# relay_pwm.net
KiCad netlist of a schematic drawn in EAGLE
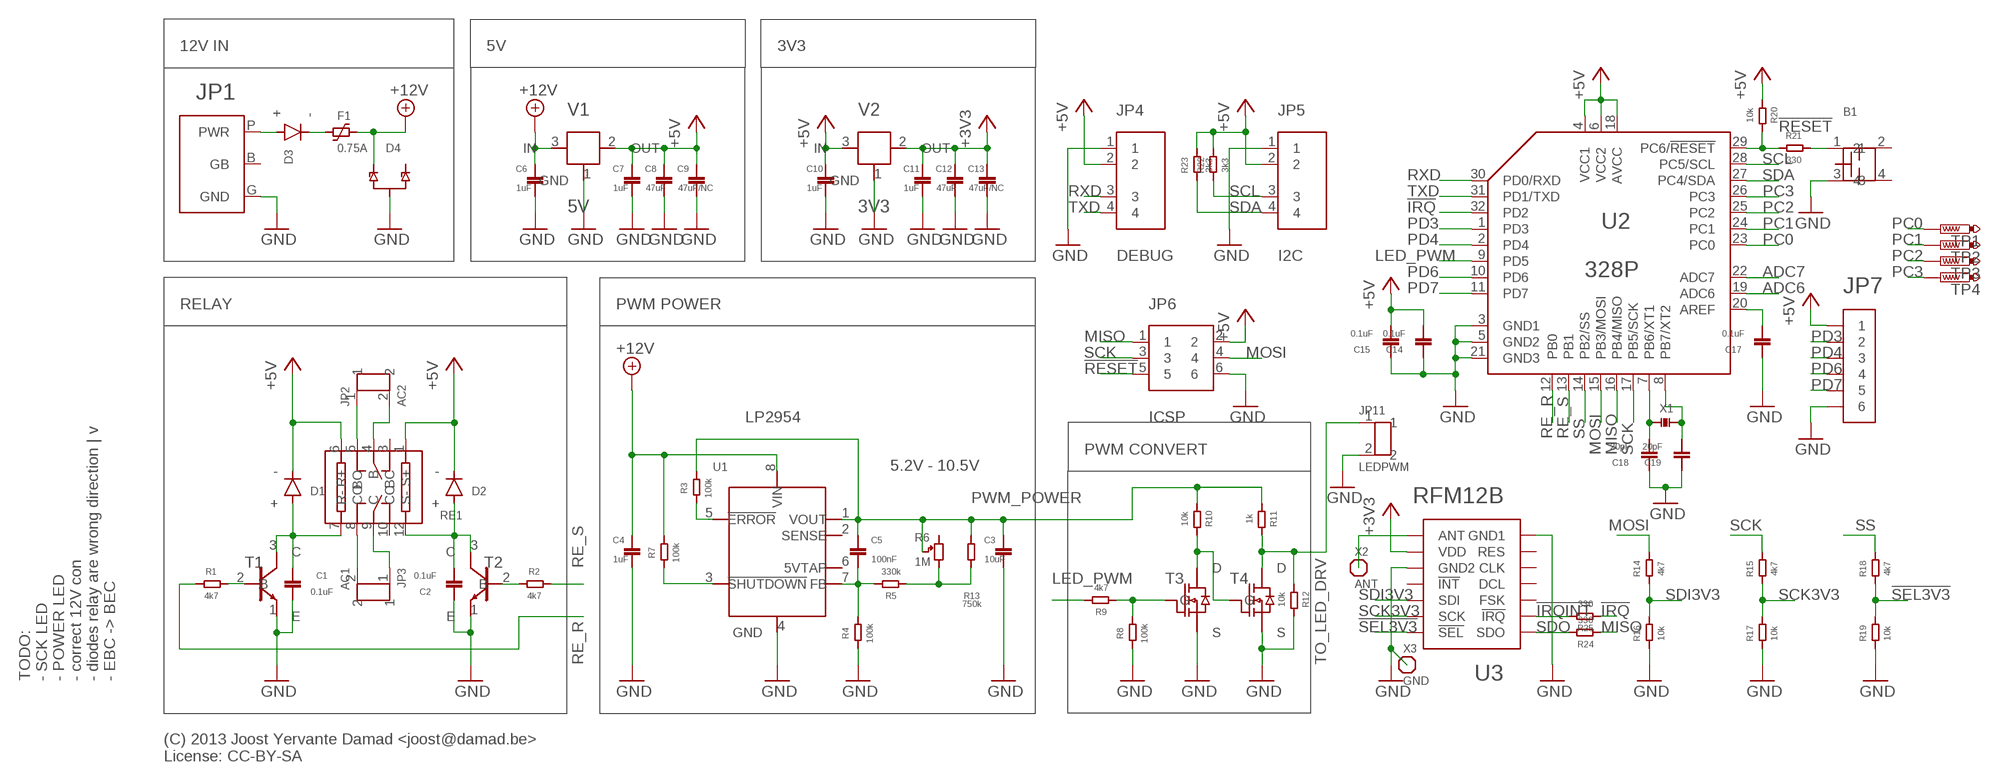
[diagram p0: schematic, sheet 1]

(export (version "E")
  (design (tool "Eeschema 10.0.6"))
  (components
    (comp (ref "B1")
      (value "BUTTON_ALPS_5.2MM_SMD")
      (footprint "eagle-import:BUTTON_ALPS_SMD_5.2MM_SKQG")
      (libsource (lib "eagle-import") (part "BUTTON_ALPS_5.2MM_SMD"))
    )
    (comp (ref "C1")
      (value "0.1uF")
      (footprint "eagle-import:0603@1")
      (libsource (lib "eagle-import") (part "C0603"))
    )
    (comp (ref "C2")
      (value "0.1uF")
      (footprint "eagle-import:0603@1")
      (libsource (lib "eagle-import") (part "C0603"))
    )
    (comp (ref "C3")
      (value "10uF")
      (footprint "eagle-import:1206")
      (libsource (lib "eagle-import") (part "CAPACITOR1206"))
    )
    (comp (ref "C4")
      (value "1uF")
      (footprint "eagle-import:0603")
      (libsource (lib "eagle-import") (part "CAPACITOR0603"))
    )
    (comp (ref "C5")
      (value "100nF")
      (footprint "eagle-import:0603")
      (libsource (lib "eagle-import") (part "CAPACITOR0603"))
    )
    (comp (ref "C6")
      (value "1uF")
      (footprint "eagle-import:0603")
      (libsource (lib "eagle-import") (part "CAPACITOR0603"))
    )
    (comp (ref "C7")
      (value "1uF")
      (footprint "eagle-import:0603")
      (libsource (lib "eagle-import") (part "CAPACITOR0603"))
    )
    (comp (ref "C8")
      (value "47uF")
      (footprint "eagle-import:1206")
      (libsource (lib "eagle-import") (part "CAPACITOR1206"))
    )
    (comp (ref "C9")
      (value "47uF/NC")
      (footprint "eagle-import:1206")
      (libsource (lib "eagle-import") (part "CAPACITOR1206"))
    )
    (comp (ref "C10")
      (value "1uF")
      (footprint "eagle-import:0603")
      (libsource (lib "eagle-import") (part "CAPACITOR0603"))
    )
    (comp (ref "C11")
      (value "1uF")
      (footprint "eagle-import:0603")
      (libsource (lib "eagle-import") (part "CAPACITOR0603"))
    )
    (comp (ref "C12")
      (value "47uF")
      (footprint "eagle-import:1206")
      (libsource (lib "eagle-import") (part "CAPACITOR1206"))
    )
    (comp (ref "C13")
      (value "47uF/NC")
      (footprint "eagle-import:1206")
      (libsource (lib "eagle-import") (part "CAPACITOR1206"))
    )
    (comp (ref "C14")
      (value "0.1uF")
      (footprint "eagle-import:0603@1")
      (libsource (lib "eagle-import") (part "C0603"))
    )
    (comp (ref "C15")
      (value "0.1uF")
      (footprint "eagle-import:0603@1")
      (libsource (lib "eagle-import") (part "C0603"))
    )
    (comp (ref "C17")
      (value "0.1uF")
      (footprint "eagle-import:0603@1")
      (libsource (lib "eagle-import") (part "C0603"))
    )
    (comp (ref "C18")
      (value "20pF")
      (footprint "eagle-import:0603@1")
      (libsource (lib "eagle-import") (part "C0603"))
    )
    (comp (ref "C19")
      (value "20pF")
      (footprint "eagle-import:0603@1")
      (libsource (lib "eagle-import") (part "C0603"))
    )
    (comp (ref "D1")
      (value "DIODE")
      (footprint "eagle-import:TAIW_SEM_DIODE")
      (libsource (lib "eagle-import") (part "DIODE"))
    )
    (comp (ref "D2")
      (value "DIODE")
      (footprint "eagle-import:TAIW_SEM_DIODE")
      (libsource (lib "eagle-import") (part "DIODE"))
    )
    (comp (ref "D3")
      (value "DIODE")
      (footprint "eagle-import:TAIW_SEM_DIODE")
      (libsource (lib "eagle-import") (part "DIODE"))
    )
    (comp (ref "D4")
      (value "DUAL_TVSSOT-23")
      (footprint "eagle-import:SOT-23")
      (libsource (lib "eagle-import") (part "DUAL_TVSSOT-23"))
    )
    (comp (ref "F1")
      (value "0.75A")
      (footprint "eagle-import:TE_POLYFUSE_1812")
      (libsource (lib "eagle-import") (part "TE_POLYFUSE_1812"))
    )
    (comp (ref "JP1")
      (value "POWER_PLUG_2.1MM")
      (footprint "eagle-import:POWER_PLUG_2.1MM")
      (libsource (lib "eagle-import") (part "POWER_PLUG_2.1MM"))
    )
    (comp (ref "JP2")
      (value "AC2")
      (footprint "eagle-import:WAGO_500_SCREW_TERMINAL_2_PIN")
      (libsource (lib "eagle-import") (part "WAGO500-2PIN"))
    )
    (comp (ref "JP3")
      (value "AC1")
      (footprint "eagle-import:WAGO_500_SCREW_TERMINAL_2_PIN")
      (libsource (lib "eagle-import") (part "WAGO500-2PIN"))
    )
    (comp (ref "JP4")
      (value "DEBUG")
      (footprint "eagle-import:PIN_1X4")
      (libsource (lib "eagle-import") (part "PIN1X4PTH2.54"))
    )
    (comp (ref "JP5")
      (value "I2C")
      (footprint "eagle-import:JST-S-4B-XH-A")
      (libsource (lib "eagle-import") (part "PIN1X4JSTSIDE"))
    )
    (comp (ref "JP6")
      (value "ICSP")
      (footprint "eagle-import:PIN_2X3_ALT")
      (libsource (lib "eagle-import") (part "PIN2X32X3ALT"))
    )
    (comp (ref "JP7")
      (value "PIN1X6")
      (footprint "eagle-import:PIN_1X6")
      (libsource (lib "eagle-import") (part "PIN1X6"))
    )
    (comp (ref "JP11")
      (value "LEDPWM")
      (footprint "eagle-import:WAGO_500_SCREW_TERMINAL_2_PIN")
      (libsource (lib "eagle-import") (part "WAGO500-2PIN"))
    )
    (comp (ref "R1")
      (value "4k7")
      (footprint "eagle-import:0603")
      (libsource (lib "eagle-import") (part "RESISTOR0603"))
    )
    (comp (ref "R2")
      (value "4k7")
      (footprint "eagle-import:0603")
      (libsource (lib "eagle-import") (part "RESISTOR0603"))
    )
    (comp (ref "R3")
      (value "100k")
      (footprint "eagle-import:0603")
      (libsource (lib "eagle-import") (part "RESISTOR0603"))
    )
    (comp (ref "R4")
      (value "100k")
      (footprint "eagle-import:0603")
      (libsource (lib "eagle-import") (part "RESISTOR0603"))
    )
    (comp (ref "R5")
      (value "330k")
      (footprint "eagle-import:0603")
      (libsource (lib "eagle-import") (part "RESISTOR0603"))
    )
    (comp (ref "R6")
      (value "1M")
      (footprint "eagle-import:SMT_TRIMMER_PANASONIC_EVM3Y")
      (libsource (lib "eagle-import") (part "TRIMMER"))
    )
    (comp (ref "R7")
      (value "100k")
      (footprint "eagle-import:0603")
      (libsource (lib "eagle-import") (part "RESISTOR0603"))
    )
    (comp (ref "R8")
      (value "100k")
      (footprint "eagle-import:0603")
      (libsource (lib "eagle-import") (part "RESISTOR0603"))
    )
    (comp (ref "R9")
      (value "4k7")
      (footprint "eagle-import:0603")
      (libsource (lib "eagle-import") (part "RESISTOR0603"))
    )
    (comp (ref "R10")
      (value "10k")
      (footprint "eagle-import:0603")
      (libsource (lib "eagle-import") (part "RESISTOR0603"))
    )
    (comp (ref "R11")
      (value "1k")
      (footprint "eagle-import:0603")
      (libsource (lib "eagle-import") (part "RESISTOR0603"))
    )
    (comp (ref "R12")
      (value "10k")
      (footprint "eagle-import:0603")
      (libsource (lib "eagle-import") (part "RESISTOR0603"))
    )
    (comp (ref "R13")
      (value "750k")
      (footprint "eagle-import:0603")
      (libsource (lib "eagle-import") (part "RESISTOR0603"))
    )
    (comp (ref "R14")
      (value "4k7")
      (footprint "eagle-import:0603")
      (libsource (lib "eagle-import") (part "RESISTOR0603"))
    )
    (comp (ref "R15")
      (value "4k7")
      (footprint "eagle-import:0603")
      (libsource (lib "eagle-import") (part "RESISTOR0603"))
    )
    (comp (ref "R16")
      (value "10k")
      (footprint "eagle-import:0603")
      (libsource (lib "eagle-import") (part "RESISTOR0603"))
    )
    (comp (ref "R17")
      (value "10k")
      (footprint "eagle-import:0603")
      (libsource (lib "eagle-import") (part "RESISTOR0603"))
    )
    (comp (ref "R18")
      (value "4k7")
      (footprint "eagle-import:0603")
      (libsource (lib "eagle-import") (part "RESISTOR0603"))
    )
    (comp (ref "R19")
      (value "10k")
      (footprint "eagle-import:0603")
      (libsource (lib "eagle-import") (part "RESISTOR0603"))
    )
    (comp (ref "R20")
      (value "10k")
      (footprint "eagle-import:0603")
      (libsource (lib "eagle-import") (part "RESISTOR0603"))
    )
    (comp (ref "R21")
      (value "330")
      (footprint "eagle-import:0603")
      (libsource (lib "eagle-import") (part "RESISTOR0603"))
    )
    (comp (ref "R22")
      (value "3k3")
      (footprint "eagle-import:0603")
      (libsource (lib "eagle-import") (part "RESISTOR0603"))
    )
    (comp (ref "R23")
      (value "3k3")
      (footprint "eagle-import:0603")
      (libsource (lib "eagle-import") (part "RESISTOR0603"))
    )
    (comp (ref "R24")
      (value "330")
      (footprint "eagle-import:0603")
      (libsource (lib "eagle-import") (part "RESISTOR0603"))
    )
    (comp (ref "R25")
      (value "330")
      (footprint "eagle-import:0603")
      (libsource (lib "eagle-import") (part "RESISTOR0603"))
    )
    (comp (ref "RE1")
      (value "RELAY_TE_V23079_THT_STD_2C")
      (footprint "eagle-import:RELAY_TE_V23079_THT_STANDARD_BISTABLE_2_COIL")
      (libsource (lib "eagle-import") (part "RELAY_TE_V23079_THT_STD_2C"))
    )
    (comp (ref "T1")
      (value "TRANSISTOR-BJT-NPNEBC")
      (footprint "eagle-import:SOT-23")
      (libsource (lib "eagle-import") (part "TRANSISTOR-BJT-NPNEBC"))
    )
    (comp (ref "T2")
      (value "TRANSISTOR-BJT-NPNEBC")
      (footprint "eagle-import:SOT-23")
      (libsource (lib "eagle-import") (part "TRANSISTOR-BJT-NPNEBC"))
    )
    (comp (ref "T3")
      (value "MOSFET-N-ENHGSD")
      (footprint "eagle-import:SOT-23")
      (libsource (lib "eagle-import") (part "MOSFET-N-ENHGSD"))
    )
    (comp (ref "T4")
      (value "MOSFET-N-ENHGSD")
      (footprint "eagle-import:SOT-23")
      (libsource (lib "eagle-import") (part "MOSFET-N-ENHGSD"))
    )
    (comp (ref "TP1")
      (value "PTR1B1,27")
      (footprint "eagle-import:B1,27")
      (libsource (lib "eagle-import") (part "PTR1B1,27"))
    )
    (comp (ref "TP2")
      (value "PTR1B1,27")
      (footprint "eagle-import:B1,27")
      (libsource (lib "eagle-import") (part "PTR1B1,27"))
    )
    (comp (ref "TP3")
      (value "PTR1B1,27")
      (footprint "eagle-import:B1,27")
      (libsource (lib "eagle-import") (part "PTR1B1,27"))
    )
    (comp (ref "TP4")
      (value "PTR1B1,27")
      (footprint "eagle-import:B1,27")
      (libsource (lib "eagle-import") (part "PTR1B1,27"))
    )
    (comp (ref "U1")
      (value "LP2954")
      (footprint "eagle-import:TI_LP2954_SO8")
      (libsource (lib "eagle-import") (part "LP2954"))
    )
    (comp (ref "U2")
      (value "328P")
      (footprint "eagle-import:TQFP32")
      (libsource (lib "eagle-import") (part "ATMEGA328PTQFP32"))
    )
    (comp (ref "U3")
      (value "RFM12B")
      (footprint "eagle-import:RFM12B")
      (libsource (lib "eagle-import") (part "RFM12B"))
    )
    (comp (ref "V1")
      (value "5V")
      (footprint "eagle-import:SOT-23A")
      (libsource (lib "eagle-import") (part "VREG_MCP1703"))
    )
    (comp (ref "V2")
      (value "3V3")
      (footprint "eagle-import:SOT-23A")
      (libsource (lib "eagle-import") (part "VREG_MCP1703"))
    )
    (comp (ref "X1")
      (value "CRYSTAL")
      (footprint "eagle-import:CRYSTAL_2-PAD_5X3.2MM")
      (libsource (lib "eagle-import") (part "CRYSTAL"))
    )
    (comp (ref "X2")
      (value "ANT")
      (footprint "eagle-import:PIN_1X1")
      (libsource (lib "eagle-import") (part "PIN1X1"))
    )
    (comp (ref "X3")
      (value "GND")
      (footprint "eagle-import:PIN_1X1")
      (libsource (lib "eagle-import") (part "PIN1X1"))
    )
  )
  (nets
    (net (code "1") (name "+3V3") (class "Default")
      (node (ref "C11") (pin "2") (pinfunction "1_2") (pintype "passive"))
      (node (ref "C12") (pin "1") (pinfunction "1_1") (pintype "passive"))
      (node (ref "C13") (pin "1") (pinfunction "1_1") (pintype "passive"))
      (node (ref "U3") (pin "VDD") (pinfunction "VDD_VDD") (pintype "bidirectional"))
      (node (ref "V2") (pin "2") (pinfunction "OUT_2") (pintype "bidirectional"))
    )
    (net (code "2") (name "+5V") (class "Default")
      (node (ref "C10") (pin "2") (pinfunction "1_2") (pintype "passive"))
      (node (ref "C14") (pin "1") (pinfunction "2_1") (pintype "passive"))
      (node (ref "C15") (pin "1") (pinfunction "2_1") (pintype "passive"))
      (node (ref "C7") (pin "2") (pinfunction "1_2") (pintype "passive"))
      (node (ref "C8") (pin "1") (pinfunction "1_1") (pintype "passive"))
      (node (ref "C9") (pin "1") (pinfunction "1_1") (pintype "passive"))
      (node (ref "D1") (pin "-") (pinfunction "-_-") (pintype "bidirectional"))
      (node (ref "D2") (pin "-") (pinfunction "-_-") (pintype "bidirectional"))
      (node (ref "JP4") (pin "2") (pinfunction "2_2") (pintype "bidirectional"))
      (node (ref "JP5") (pin "2") (pinfunction "2_2") (pintype "bidirectional"))
      (node (ref "JP6") (pin "2") (pinfunction "2_2") (pintype "bidirectional"))
      (node (ref "JP7") (pin "1") (pinfunction "1_1") (pintype "bidirectional"))
      (node (ref "R20") (pin "1") (pinfunction "1_1") (pintype "passive"))
      (node (ref "R22") (pin "2") (pinfunction "2_2") (pintype "passive"))
      (node (ref "R23") (pin "2") (pinfunction "2_2") (pintype "passive"))
      (node (ref "RE1") (pin "1") (pinfunction "S+_1") (pintype "bidirectional"))
      (node (ref "RE1") (pin "6") (pinfunction "R+_6") (pintype "bidirectional"))
      (node (ref "U2") (pin "18") (pinfunction "AVCC_18") (pintype "bidirectional"))
      (node (ref "U2") (pin "4") (pinfunction "VCC1_4") (pintype "bidirectional"))
      (node (ref "U2") (pin "6") (pinfunction "VCC2_6") (pintype "bidirectional"))
      (node (ref "V1") (pin "2") (pinfunction "OUT_2") (pintype "bidirectional"))
      (node (ref "V2") (pin "3") (pinfunction "IN_3") (pintype "bidirectional"))
    )
    (net (code "3") (name "+12V") (class "Default")
      (node (ref "C4") (pin "2") (pinfunction "1_2") (pintype "passive"))
      (node (ref "C6") (pin "2") (pinfunction "1_2") (pintype "passive"))
      (node (ref "D4") (pin "1") (pinfunction "P1_1") (pintype "bidirectional"))
      (node (ref "F1") (pin "2") (pinfunction "P$2_2") (pintype "bidirectional"))
      (node (ref "R7") (pin "2") (pinfunction "2_2") (pintype "passive"))
      (node (ref "U1") (pin "8") (pinfunction "VIN_8") (pintype "power_in"))
      (node (ref "V1") (pin "3") (pinfunction "IN_3") (pintype "bidirectional"))
    )
    (net (code "4") (name "/ADC6") (class "Default")
      (node (ref "U2") (pin "19") (pinfunction "ADC6_19") (pintype "bidirectional"))
    )
    (net (code "5") (name "/ADC7") (class "Default")
      (node (ref "U2") (pin "22") (pinfunction "ADC7_22") (pintype "bidirectional"))
    )
    (net (code "6") (name "/LED_PWM") (class "Default")
      (node (ref "R9") (pin "2") (pinfunction "2_2") (pintype "passive"))
      (node (ref "U2") (pin "9") (pinfunction "PD5_9") (pintype "bidirectional"))
    )
    (net (code "7") (name "/MISO") (class "Default")
      (node (ref "JP6") (pin "1") (pinfunction "1_1") (pintype "bidirectional"))
      (node (ref "R24") (pin "1") (pinfunction "1_1") (pintype "passive"))
      (node (ref "U2") (pin "16") (pinfunction "PB4/MISO_16") (pintype "bidirectional"))
    )
    (net (code "8") (name "/MOSI") (class "Default")
      (node (ref "JP6") (pin "4") (pinfunction "4_4") (pintype "bidirectional"))
      (node (ref "R14") (pin "2") (pinfunction "2_2") (pintype "passive"))
      (node (ref "U2") (pin "15") (pinfunction "PB3/MOSI_15") (pintype "bidirectional"))
    )
    (net (code "9") (name "/PC0") (class "Default")
      (node (ref "TP1") (pin "TP") (pinfunction "TP_TP") (pintype "input"))
      (node (ref "U2") (pin "23") (pinfunction "PC0_23") (pintype "bidirectional"))
    )
    (net (code "10") (name "/PC1") (class "Default")
      (node (ref "TP2") (pin "TP") (pinfunction "TP_TP") (pintype "input"))
      (node (ref "U2") (pin "24") (pinfunction "PC1_24") (pintype "bidirectional"))
    )
    (net (code "11") (name "/PC2") (class "Default")
      (node (ref "TP3") (pin "TP") (pinfunction "TP_TP") (pintype "input"))
      (node (ref "U2") (pin "25") (pinfunction "PC2_25") (pintype "bidirectional"))
    )
    (net (code "12") (name "/PC3") (class "Default")
      (node (ref "TP4") (pin "TP") (pinfunction "TP_TP") (pintype "input"))
      (node (ref "U2") (pin "26") (pinfunction "PC3_26") (pintype "bidirectional"))
    )
    (net (code "13") (name "/PD3") (class "Default")
      (node (ref "JP7") (pin "2") (pinfunction "2_2") (pintype "bidirectional"))
      (node (ref "U2") (pin "1") (pinfunction "PD3_1") (pintype "bidirectional"))
    )
    (net (code "14") (name "/PD4") (class "Default")
      (node (ref "JP7") (pin "3") (pinfunction "3_3") (pintype "bidirectional"))
      (node (ref "U2") (pin "2") (pinfunction "PD4_2") (pintype "bidirectional"))
    )
    (net (code "15") (name "/PD6") (class "Default")
      (node (ref "JP7") (pin "4") (pinfunction "4_4") (pintype "bidirectional"))
      (node (ref "U2") (pin "10") (pinfunction "PD6_10") (pintype "bidirectional"))
    )
    (net (code "16") (name "/PD7") (class "Default")
      (node (ref "JP7") (pin "5") (pinfunction "5_5") (pintype "bidirectional"))
      (node (ref "U2") (pin "11") (pinfunction "PD7_11") (pintype "bidirectional"))
    )
    (net (code "17") (name "/PWM_POWER") (class "Default")
      (node (ref "C3") (pin "1") (pinfunction "1_1") (pintype "passive"))
      (node (ref "C5") (pin "2") (pinfunction "1_2") (pintype "passive"))
      (node (ref "R10") (pin "1") (pinfunction "1_1") (pintype "passive"))
      (node (ref "R11") (pin "1") (pinfunction "1_1") (pintype "passive"))
      (node (ref "R13") (pin "2") (pinfunction "2_2") (pintype "passive"))
      (node (ref "R3") (pin "2") (pinfunction "2_2") (pintype "passive"))
      (node (ref "R6") (pin "B") (pinfunction "3_B") (pintype "bidirectional"))
      (node (ref "U1") (pin "1") (pinfunction "VOUT_1") (pintype "bidirectional"))
    )
    (net (code "18") (name "/RE_R") (class "Default")
      (node (ref "R1") (pin "1") (pinfunction "1_1") (pintype "passive"))
      (node (ref "U2") (pin "12") (pinfunction "PB0_12") (pintype "bidirectional"))
    )
    (net (code "19") (name "/RE_S") (class "Default")
      (node (ref "R2") (pin "2") (pinfunction "2_2") (pintype "passive"))
      (node (ref "U2") (pin "13") (pinfunction "PB1_13") (pintype "bidirectional"))
    )
    (net (code "20") (name "/RXD") (class "Default")
      (node (ref "JP4") (pin "3") (pinfunction "3_3") (pintype "bidirectional"))
      (node (ref "U2") (pin "30") (pinfunction "PD0/RXD_30") (pintype "bidirectional"))
    )
    (net (code "21") (name "/SCK") (class "Default")
      (node (ref "JP6") (pin "3") (pinfunction "3_3") (pintype "bidirectional"))
      (node (ref "R15") (pin "2") (pinfunction "2_2") (pintype "passive"))
      (node (ref "U2") (pin "17") (pinfunction "PB5/SCK_17") (pintype "bidirectional"))
    )
    (net (code "22") (name "/SCK3V3") (class "Default")
      (node (ref "R15") (pin "1") (pinfunction "1_1") (pintype "passive"))
      (node (ref "R17") (pin "2") (pinfunction "2_2") (pintype "passive"))
      (node (ref "U3") (pin "SCK") (pinfunction "SCK_SCK") (pintype "bidirectional"))
    )
    (net (code "23") (name "/SCL") (class "Default")
      (node (ref "JP5") (pin "3") (pinfunction "3_3") (pintype "bidirectional"))
      (node (ref "R22") (pin "1") (pinfunction "1_1") (pintype "passive"))
      (node (ref "U2") (pin "28") (pinfunction "PC5/SCL_28") (pintype "bidirectional"))
    )
    (net (code "24") (name "/SDA") (class "Default")
      (node (ref "JP5") (pin "4") (pinfunction "4_4") (pintype "bidirectional"))
      (node (ref "R23") (pin "1") (pinfunction "1_1") (pintype "passive"))
      (node (ref "U2") (pin "27") (pinfunction "PC4/SDA_27") (pintype "bidirectional"))
    )
    (net (code "25") (name "/SDI3V3") (class "Default")
      (node (ref "R14") (pin "1") (pinfunction "1_1") (pintype "passive"))
      (node (ref "R16") (pin "2") (pinfunction "2_2") (pintype "passive"))
      (node (ref "U3") (pin "SDI") (pinfunction "SDI_SDI") (pintype "bidirectional"))
    )
    (net (code "26") (name "/SDO") (class "Default")
      (node (ref "R24") (pin "2") (pinfunction "2_2") (pintype "passive"))
      (node (ref "U3") (pin "SDO") (pinfunction "SDO_SDO") (pintype "bidirectional"))
    )
    (net (code "27") (name "/SS") (class "Default")
      (node (ref "R18") (pin "2") (pinfunction "2_2") (pintype "passive"))
      (node (ref "U2") (pin "14") (pinfunction "PB2/SS_14") (pintype "bidirectional"))
    )
    (net (code "28") (name "/TO_LED_DRV") (class "Default")
      (node (ref "JP11") (pin "1") (pinfunction "1_1") (pintype "bidirectional"))
      (node (ref "R11") (pin "2") (pinfunction "2_2") (pintype "passive"))
      (node (ref "R12") (pin "1") (pinfunction "1_1") (pintype "passive"))
      (node (ref "T4") (pin "3") (pinfunction "D_3") (pintype "bidirectional"))
    )
    (net (code "29") (name "/TXD") (class "Default")
      (node (ref "JP4") (pin "4") (pinfunction "4_4") (pintype "bidirectional"))
      (node (ref "U2") (pin "31") (pinfunction "PD1/TXD_31") (pintype "bidirectional"))
    )
    (net (code "30") (name "/~{IRQINT}") (class "Default")
      (node (ref "R25") (pin "2") (pinfunction "2_2") (pintype "passive"))
      (node (ref "U3") (pin "NIRQ") (pinfunction "~{IRQ}_NIRQ") (pintype "bidirectional"))
    )
    (net (code "31") (name "/~{IRQ}") (class "Default")
      (node (ref "R25") (pin "1") (pinfunction "1_1") (pintype "passive"))
      (node (ref "U2") (pin "32") (pinfunction "PD2_32") (pintype "bidirectional"))
    )
    (net (code "32") (name "/~{RESET}") (class "Default")
      (node (ref "JP6") (pin "5") (pinfunction "5_5") (pintype "bidirectional"))
      (node (ref "R20") (pin "2") (pinfunction "2_2") (pintype "passive"))
      (node (ref "R21") (pin "1") (pinfunction "1_1") (pintype "passive"))
      (node (ref "U2") (pin "29") (pinfunction "PC6/~{RESET}_29") (pintype "bidirectional"))
    )
    (net (code "33") (name "/~{SEL3V3}") (class "Default")
      (node (ref "R18") (pin "1") (pinfunction "1_1") (pintype "passive"))
      (node (ref "R19") (pin "2") (pinfunction "2_2") (pintype "passive"))
      (node (ref "U3") (pin "NSEL") (pinfunction "~{SEL}_NSEL") (pintype "bidirectional"))
    )
    (net (code "34") (name "GND") (class "Default")
      (node (ref "B1") (pin "3") (pinfunction "3_3") (pintype "bidirectional"))
      (node (ref "C1") (pin "1") (pinfunction "2_1") (pintype "passive"))
      (node (ref "C10") (pin "1") (pinfunction "2_1") (pintype "passive"))
      (node (ref "C11") (pin "1") (pinfunction "2_1") (pintype "passive"))
      (node (ref "C12") (pin "2") (pinfunction "2_2") (pintype "passive"))
      (node (ref "C13") (pin "2") (pinfunction "2_2") (pintype "passive"))
      (node (ref "C14") (pin "2") (pinfunction "1_2") (pintype "passive"))
      (node (ref "C15") (pin "2") (pinfunction "1_2") (pintype "passive"))
      (node (ref "C17") (pin "2") (pinfunction "1_2") (pintype "passive"))
      (node (ref "C18") (pin "2") (pinfunction "1_2") (pintype "passive"))
      (node (ref "C19") (pin "2") (pinfunction "1_2") (pintype "passive"))
      (node (ref "C2") (pin "2") (pinfunction "1_2") (pintype "passive"))
      (node (ref "C3") (pin "2") (pinfunction "2_2") (pintype "passive"))
      (node (ref "C4") (pin "1") (pinfunction "2_1") (pintype "passive"))
      (node (ref "C6") (pin "1") (pinfunction "2_1") (pintype "passive"))
      (node (ref "C7") (pin "1") (pinfunction "2_1") (pintype "passive"))
      (node (ref "C8") (pin "2") (pinfunction "2_2") (pintype "passive"))
      (node (ref "C9") (pin "2") (pinfunction "2_2") (pintype "passive"))
      (node (ref "D4") (pin "3") (pinfunction "G1_3") (pintype "bidirectional"))
      (node (ref "JP1") (pin "G") (pinfunction "GND_G") (pintype "bidirectional"))
      (node (ref "JP11") (pin "2") (pinfunction "2_2") (pintype "bidirectional"))
      (node (ref "JP4") (pin "1") (pinfunction "1_1") (pintype "bidirectional"))
      (node (ref "JP5") (pin "1") (pinfunction "1_1") (pintype "bidirectional"))
      (node (ref "JP6") (pin "6") (pinfunction "6_6") (pintype "bidirectional"))
      (node (ref "JP7") (pin "6") (pinfunction "6_6") (pintype "bidirectional"))
      (node (ref "R12") (pin "2") (pinfunction "2_2") (pintype "passive"))
      (node (ref "R16") (pin "1") (pinfunction "1_1") (pintype "passive"))
      (node (ref "R17") (pin "1") (pinfunction "1_1") (pintype "passive"))
      (node (ref "R19") (pin "1") (pinfunction "1_1") (pintype "passive"))
      (node (ref "R4") (pin "1") (pinfunction "1_1") (pintype "passive"))
      (node (ref "R8") (pin "1") (pinfunction "1_1") (pintype "passive"))
      (node (ref "T1") (pin "1") (pinfunction "E_1") (pintype "bidirectional"))
      (node (ref "T2") (pin "1") (pinfunction "E_1") (pintype "bidirectional"))
      (node (ref "T3") (pin "2") (pinfunction "S_2") (pintype "bidirectional"))
      (node (ref "T4") (pin "2") (pinfunction "S_2") (pintype "bidirectional"))
      (node (ref "U1") (pin "4") (pinfunction "GND_4") (pintype "power_in"))
      (node (ref "U2") (pin "21") (pinfunction "GND3_21") (pintype "bidirectional"))
      (node (ref "U2") (pin "3") (pinfunction "GND1_3") (pintype "bidirectional"))
      (node (ref "U2") (pin "5") (pinfunction "GND2_5") (pintype "bidirectional"))
      (node (ref "U3") (pin "GND@1") (pinfunction "GND1_GND@1") (pintype "bidirectional"))
      (node (ref "U3") (pin "GND@2") (pinfunction "GND2_GND@2") (pintype "bidirectional"))
      (node (ref "V1") (pin "1") (pinfunction "GND_1") (pintype "bidirectional"))
      (node (ref "V2") (pin "1") (pinfunction "GND_1") (pintype "bidirectional"))
      (node (ref "X3") (pin "1") (pinfunction "P$1_1") (pintype "bidirectional"))
    )
    (net (code "35") (name "Net-(B1-Pad1)") (class "Default")
      (node (ref "B1") (pin "1") (pinfunction "1_1") (pintype "bidirectional"))
      (node (ref "R21") (pin "2") (pinfunction "2_2") (pintype "passive"))
    )
    (net (code "36") (name "Net-(C1-1)") (class "Default")
      (node (ref "C1") (pin "2") (pinfunction "1_2") (pintype "passive"))
      (node (ref "D1") (pin "+") (pinfunction "+_+") (pintype "bidirectional"))
      (node (ref "RE1") (pin "7") (pinfunction "R-_7") (pintype "bidirectional"))
      (node (ref "T1") (pin "3") (pinfunction "C_3") (pintype "bidirectional"))
    )
    (net (code "37") (name "Net-(C2-2)") (class "Default")
      (node (ref "C2") (pin "1") (pinfunction "2_1") (pintype "passive"))
      (node (ref "D2") (pin "+") (pinfunction "+_+") (pintype "bidirectional"))
      (node (ref "RE1") (pin "12") (pinfunction "S-_12") (pintype "bidirectional"))
      (node (ref "T2") (pin "3") (pinfunction "C_3") (pintype "bidirectional"))
    )
    (net (code "38") (name "Net-(C5-2)") (class "Default")
      (node (ref "C5") (pin "1") (pinfunction "2_1") (pintype "passive"))
      (node (ref "R4") (pin "2") (pinfunction "2_2") (pintype "passive"))
      (node (ref "R5") (pin "2") (pinfunction "2_2") (pintype "passive"))
      (node (ref "U1") (pin "7") (pinfunction "FB_7") (pintype "bidirectional"))
    )
    (net (code "39") (name "Net-(C17-2)") (class "Default")
      (node (ref "C17") (pin "1") (pinfunction "2_1") (pintype "passive"))
      (node (ref "U2") (pin "20") (pinfunction "AREF_20") (pintype "bidirectional"))
    )
    (net (code "40") (name "Net-(C18-2)") (class "Default")
      (node (ref "C18") (pin "1") (pinfunction "2_1") (pintype "passive"))
      (node (ref "U2") (pin "7") (pinfunction "PB6/XT1_7") (pintype "bidirectional"))
      (node (ref "X1") (pin "1") (pinfunction "P$1_1") (pintype "bidirectional"))
    )
    (net (code "41") (name "Net-(C19-2)") (class "Default")
      (node (ref "C19") (pin "1") (pinfunction "2_1") (pintype "passive"))
      (node (ref "U2") (pin "8") (pinfunction "PB7/XT2_8") (pintype "bidirectional"))
      (node (ref "X1") (pin "2") (pinfunction "P$2_2") (pintype "bidirectional"))
    )
    (net (code "42") (name "Net-(F1-P$1)") (class "Default")
      (node (ref "D3") (pin "-") (pinfunction "-_-") (pintype "bidirectional"))
      (node (ref "F1") (pin "1") (pinfunction "P$1_1") (pintype "bidirectional"))
    )
    (net (code "43") (name "Net-(JP1-PWR)") (class "Default")
      (node (ref "D3") (pin "+") (pinfunction "+_+") (pintype "bidirectional"))
      (node (ref "JP1") (pin "P") (pinfunction "PWR_P") (pintype "bidirectional"))
    )
    (net (code "44") (name "Net-(R6-2)") (class "Default")
      (node (ref "R13") (pin "1") (pinfunction "1_1") (pintype "passive"))
      (node (ref "R5") (pin "1") (pinfunction "1_1") (pintype "passive"))
      (node (ref "R6") (pin "C") (pinfunction "2_C") (pintype "bidirectional"))
    )
    (net (code "45") (name "Net-(RE1-B)") (class "Default")
      (node (ref "JP2") (pin "2") (pinfunction "2_2") (pintype "bidirectional"))
      (node (ref "RE1") (pin "4") (pinfunction "B_4") (pintype "bidirectional"))
    )
    (net (code "46") (name "Net-(RE1-BO)") (class "Default")
      (node (ref "JP2") (pin "1") (pinfunction "1_1") (pintype "bidirectional"))
      (node (ref "RE1") (pin "5") (pinfunction "BO_5") (pintype "bidirectional"))
    )
    (net (code "47") (name "Net-(RE1-C)") (class "Default")
      (node (ref "JP3") (pin "1") (pinfunction "1_1") (pintype "bidirectional"))
      (node (ref "RE1") (pin "9") (pinfunction "C_9") (pintype "bidirectional"))
    )
    (net (code "48") (name "Net-(RE1-CO)") (class "Default")
      (node (ref "JP3") (pin "2") (pinfunction "2_2") (pintype "bidirectional"))
      (node (ref "RE1") (pin "8") (pinfunction "CO_8") (pintype "bidirectional"))
    )
    (net (code "49") (name "Net-(T1-B)") (class "Default")
      (node (ref "R1") (pin "2") (pinfunction "2_2") (pintype "passive"))
      (node (ref "T1") (pin "2") (pinfunction "B_2") (pintype "bidirectional"))
    )
    (net (code "50") (name "Net-(T2-B)") (class "Default")
      (node (ref "R2") (pin "1") (pinfunction "1_1") (pintype "passive"))
      (node (ref "T2") (pin "2") (pinfunction "B_2") (pintype "bidirectional"))
    )
    (net (code "51") (name "Net-(T3-D)") (class "Default")
      (node (ref "R10") (pin "2") (pinfunction "2_2") (pintype "passive"))
      (node (ref "T3") (pin "3") (pinfunction "D_3") (pintype "bidirectional"))
      (node (ref "T4") (pin "1") (pinfunction "G_1") (pintype "bidirectional"))
    )
    (net (code "52") (name "Net-(T3-G)") (class "Default")
      (node (ref "R8") (pin "2") (pinfunction "2_2") (pintype "passive"))
      (node (ref "R9") (pin "1") (pinfunction "1_1") (pintype "passive"))
      (node (ref "T3") (pin "1") (pinfunction "G_1") (pintype "bidirectional"))
    )
    (net (code "53") (name "Net-(U1-~{ERROR})") (class "Default")
      (node (ref "R3") (pin "1") (pinfunction "1_1") (pintype "passive"))
      (node (ref "U1") (pin "5") (pinfunction "~{ERROR}_5") (pintype "bidirectional"))
    )
    (net (code "54") (name "Net-(U1-~{SHUTDOWN})") (class "Default")
      (node (ref "R7") (pin "1") (pinfunction "1_1") (pintype "passive"))
      (node (ref "U1") (pin "3") (pinfunction "~{SHUTDOWN}_3") (pintype "bidirectional"))
    )
    (net (code "55") (name "Net-(X2-P$1)") (class "Default")
      (node (ref "U3") (pin "ANT") (pinfunction "ANT_ANT") (pintype "bidirectional"))
      (node (ref "X2") (pin "1") (pinfunction "P$1_1") (pintype "bidirectional"))
    )
    (net (code "56") (name "unconnected-(B1-Pad2)") (class "Default")
      (node (ref "B1") (pin "2") (pinfunction "2_2") (pintype "bidirectional"))
    )
    (net (code "57") (name "unconnected-(B1-Pad4)") (class "Default")
      (node (ref "B1") (pin "4") (pinfunction "4_4") (pintype "bidirectional"))
    )
    (net (code "58") (name "unconnected-(D4-P2-Pad2)") (class "Default")
      (node (ref "D4") (pin "2") (pinfunction "P2_2") (pintype "bidirectional"))
    )
    (net (code "59") (name "unconnected-(JP1-GB-PadB)") (class "Default")
      (node (ref "JP1") (pin "B") (pinfunction "GB_B") (pintype "bidirectional"))
    )
    (net (code "60") (name "unconnected-(R6-1-PadA)") (class "Default")
      (node (ref "R6") (pin "A") (pinfunction "1_A") (pintype "bidirectional"))
    )
    (net (code "61") (name "unconnected-(RE1-BC-Pad3)") (class "Default")
      (node (ref "RE1") (pin "3") (pinfunction "BC_3") (pintype "bidirectional"))
    )
    (net (code "62") (name "unconnected-(RE1-CC-Pad10)") (class "Default")
      (node (ref "RE1") (pin "10") (pinfunction "CC_10") (pintype "bidirectional"))
    )
    (net (code "63") (name "unconnected-(U1-5VTAP-Pad6)") (class "Default")
      (node (ref "U1") (pin "6") (pinfunction "5VTAP_6") (pintype "bidirectional"))
    )
    (net (code "64") (name "unconnected-(U1-SENSE-Pad2)") (class "Default")
      (node (ref "U1") (pin "2") (pinfunction "SENSE_2") (pintype "bidirectional"))
    )
    (net (code "65") (name "unconnected-(U3-PadCLK)") (class "Default")
      (node (ref "U3") (pin "CLK") (pinfunction "CLK_CLK") (pintype "bidirectional"))
    )
    (net (code "66") (name "unconnected-(U3-PadDCL)") (class "Default")
      (node (ref "U3") (pin "DCL") (pinfunction "DCL_DCL") (pintype "bidirectional"))
    )
    (net (code "67") (name "unconnected-(U3-PadFSK)") (class "Default")
      (node (ref "U3") (pin "FSK") (pinfunction "FSK_FSK") (pintype "bidirectional"))
    )
    (net (code "68") (name "unconnected-(U3-PadRES)") (class "Default")
      (node (ref "U3") (pin "RES") (pinfunction "RES_RES") (pintype "bidirectional"))
    )
    (net (code "69") (name "unconnected-(U3-~{INT}-PadNINT)") (class "Default")
      (node (ref "U3") (pin "NINT") (pinfunction "~{INT}_NINT") (pintype "bidirectional"))
    )
  )
)
